# OL_sensor_assy_FPC.net
KiCad netlist of a schematic drawn in Altium Designer
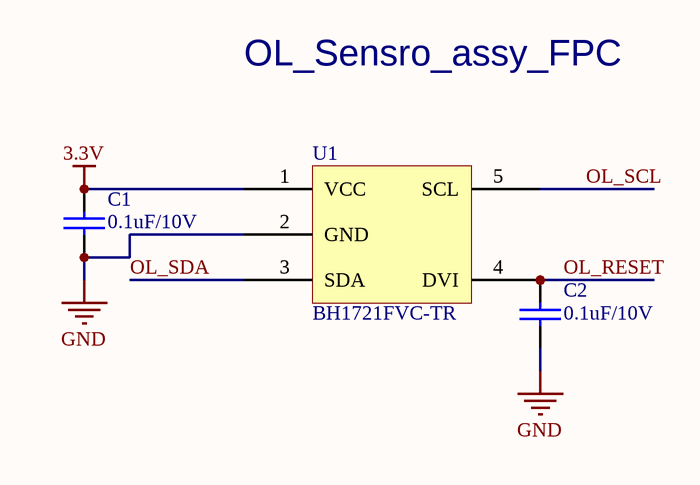
[diagram p0: OL_sensor_assy FPC.SchDoc]

(export (version "E")
  (design (tool "Eeschema 10.0.6"))
  (components
    (comp (ref "C1")
      (value "0.1uF/10V")
      (footprint "0402C")
      (description "厂家：Murata，型号：")
      (libsource (lib "*") (part "CAP"))
    )
    (comp (ref "C2")
      (value "0.1uF/10V")
      (footprint "0402C")
      (description "厂家：Murata，型号：")
      (libsource (lib "*") (part "CAP"))
    )
    (comp (ref "U1")
      (value "BH1721FVC-TR")
      (footprint "WSOF5")
      (libsource (lib "Schlib1") (part "BH1721FVC-TR"))
    )
  )
  (nets
    (net (code "1") (name "/OL_RESET") (class "Default")
      (node (ref "C2") (pin "1") (pinfunction "1_1") (pintype "passive"))
      (node (ref "U1") (pin "4") (pinfunction "DVI_4") (pintype "passive"))
    )
    (net (code "2") (name "/OL_SCL") (class "Default")
      (node (ref "U1") (pin "5") (pinfunction "SCL_5") (pintype "passive"))
    )
    (net (code "3") (name "/OL_SDA") (class "Default")
      (node (ref "U1") (pin "3") (pinfunction "SDA_3") (pintype "passive"))
    )
    (net (code "4") (name "3.3V") (class "Default")
      (node (ref "C1") (pin "1") (pinfunction "1_1") (pintype "passive"))
      (node (ref "U1") (pin "1") (pinfunction "VCC_1") (pintype "passive"))
    )
    (net (code "5") (name "GND") (class "Default")
      (node (ref "C1") (pin "2") (pinfunction "2_2") (pintype "passive"))
      (node (ref "C2") (pin "2") (pinfunction "2_2") (pintype "passive"))
      (node (ref "U1") (pin "2") (pinfunction "GND_2") (pintype "passive"))
    )
  )
)
